# Input_0.net
KiCad netlist of a schematic drawn in Altium Designer
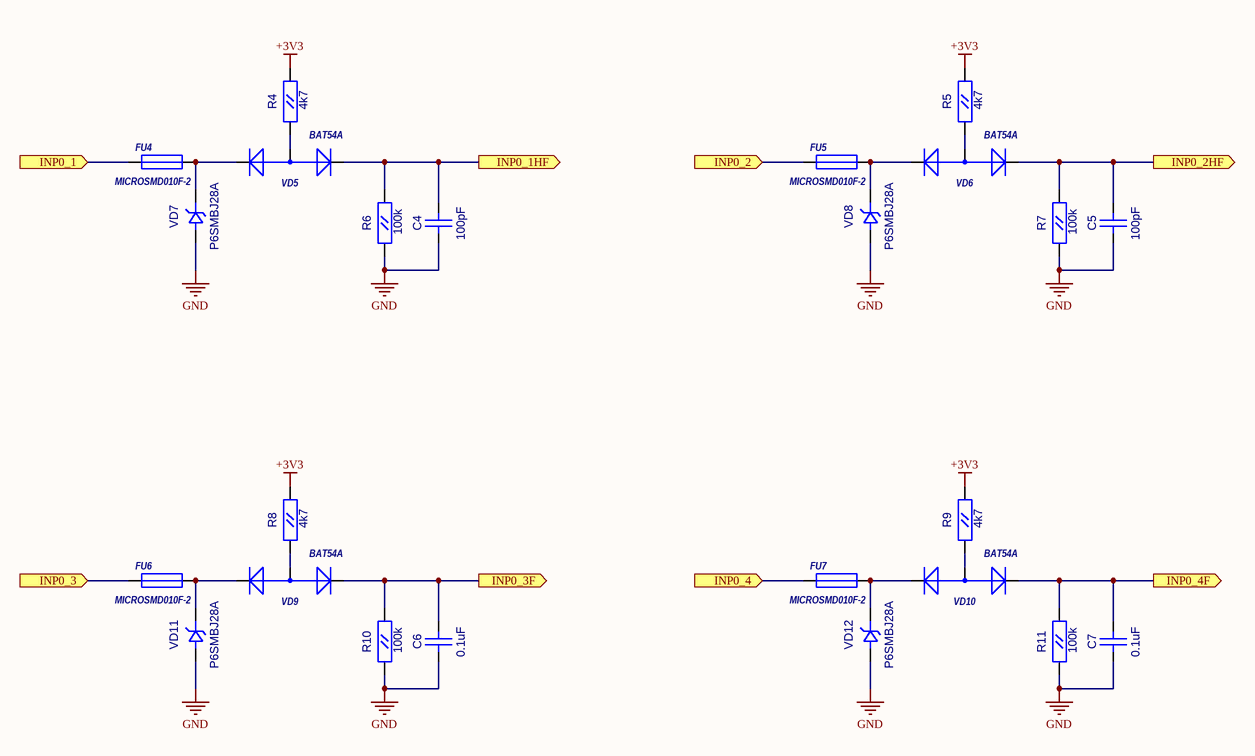
[diagram p0: Input_0.SchDoc]

(export (version "E")
  (design (tool "Eeschema 10.0.6"))
  (components
    (comp (ref "C4")
      (value "100pF")
      (footprint "CC0603")
      (description "CC0603")
      (libsource (lib "gprs_modem_2") (part "CC0603"))
    )
    (comp (ref "C5")
      (value "100pF")
      (footprint "CC0603")
      (description "CC0603")
      (libsource (lib "gprs_modem_2") (part "CC0603"))
    )
    (comp (ref "C6")
      (value "0.1uF")
      (footprint "CC0603")
      (description "CC0603")
      (libsource (lib "gprs_modem_2") (part "CC0603"))
    )
    (comp (ref "C7")
      (value "0.1uF")
      (footprint "CC0603")
      (description "CC0603")
      (libsource (lib "gprs_modem_2") (part "CC0603"))
    )
    (comp (ref "FU4")
      (value "MICROSMD010F-2")
      (footprint "RC1210")
      (description "MICROSMD")
      (libsource (lib "gprs_modem_2") (part "MICROSMD"))
    )
    (comp (ref "FU5")
      (value "MICROSMD010F-2")
      (footprint "RC1210")
      (description "MICROSMD")
      (libsource (lib "gprs_modem_2") (part "MICROSMD"))
    )
    (comp (ref "FU6")
      (value "MICROSMD010F-2")
      (footprint "RC1210")
      (description "MICROSMD")
      (libsource (lib "gprs_modem_2") (part "MICROSMD"))
    )
    (comp (ref "FU7")
      (value "MICROSMD010F-2")
      (footprint "RC1210")
      (description "MICROSMD")
      (libsource (lib "gprs_modem_2") (part "MICROSMD"))
    )
    (comp (ref "R4")
      (value "4k7")
      (footprint "RC0603")
      (description "RC0603")
      (libsource (lib "gprs_modem_2") (part "RC0603"))
    )
    (comp (ref "R5")
      (value "4k7")
      (footprint "RC0603")
      (description "RC0603")
      (libsource (lib "gprs_modem_2") (part "RC0603"))
    )
    (comp (ref "R6")
      (value "100k")
      (footprint "RC0603")
      (description "RC0603")
      (libsource (lib "gprs_modem_2") (part "RC0603"))
    )
    (comp (ref "R7")
      (value "100k")
      (footprint "RC0603")
      (description "RC0603")
      (libsource (lib "gprs_modem_2") (part "RC0603"))
    )
    (comp (ref "R8")
      (value "4k7")
      (footprint "RC0603")
      (description "RC0603")
      (libsource (lib "gprs_modem_2") (part "RC0603"))
    )
    (comp (ref "R9")
      (value "4k7")
      (footprint "RC0603")
      (description "RC0603")
      (libsource (lib "gprs_modem_2") (part "RC0603"))
    )
    (comp (ref "R10")
      (value "100k")
      (footprint "RC0603")
      (description "RC0603")
      (libsource (lib "gprs_modem_2") (part "RC0603"))
    )
    (comp (ref "R11")
      (value "100k")
      (footprint "RC0603")
      (description "RC0603")
      (libsource (lib "gprs_modem_2") (part "RC0603"))
    )
    (comp (ref "VD5")
      (value "BAT54A")
      (footprint "SOT-23(123)")
      (description "1.0 Ampere General Purpose Rectifier")
      (libsource (lib "gprs_modem_2") (part "BAT54A"))
    )
    (comp (ref "VD6")
      (value "BAT54A")
      (footprint "SOT-23(123)")
      (description "1.0 Ampere General Purpose Rectifier")
      (libsource (lib "gprs_modem_2") (part "BAT54A"))
    )
    (comp (ref "VD7")
      (value "P6SMBJ28A")
      (footprint "SMB")
      (description "SMBJ")
      (libsource (lib "gprs_modem_2") (part "SMBJ"))
    )
    (comp (ref "VD8")
      (value "P6SMBJ28A")
      (footprint "SMB")
      (description "SMBJ")
      (libsource (lib "gprs_modem_2") (part "SMBJ"))
    )
    (comp (ref "VD9")
      (value "BAT54A")
      (footprint "SOT-23(123)")
      (description "1.0 Ampere General Purpose Rectifier")
      (libsource (lib "gprs_modem_2") (part "BAT54A"))
    )
    (comp (ref "VD10")
      (value "BAT54A")
      (footprint "SOT-23(123)")
      (description "1.0 Ampere General Purpose Rectifier")
      (libsource (lib "gprs_modem_2") (part "BAT54A"))
    )
    (comp (ref "VD11")
      (value "P6SMBJ28A")
      (footprint "SMB")
      (description "SMBJ")
      (libsource (lib "gprs_modem_2") (part "SMBJ"))
    )
    (comp (ref "VD12")
      (value "P6SMBJ28A")
      (footprint "SMB")
      (description "SMBJ")
      (libsource (lib "gprs_modem_2") (part "SMBJ"))
    )
  )
  (nets
    (net (code "1") (name "+3V3") (class "Default")
      (node (ref "R4") (pin "2") (pinfunction "B_2") (pintype "passive"))
      (node (ref "R5") (pin "2") (pinfunction "B_2") (pintype "passive"))
      (node (ref "R8") (pin "2") (pinfunction "B_2") (pintype "passive"))
      (node (ref "R9") (pin "2") (pinfunction "B_2") (pintype "passive"))
    )
    (net (code "2") (name "/INP0_1") (class "Default") (node (ref "FU4") (pin "1") (pintype "passive")))
    (net (code "3") (name "/INP0_1HF") (class "Default")
      (node (ref "C4") (pin "2") (pinfunction "B_2") (pintype "passive"))
      (node (ref "R6") (pin "2") (pinfunction "B_2") (pintype "passive"))
      (node (ref "VD5") (pin "1") (pinfunction "K_1") (pintype "passive"))
    )
    (net (code "4") (name "/INP0_2") (class "Default") (node (ref "FU5") (pin "1") (pintype "passive")))
    (net (code "5") (name "/INP0_2HF") (class "Default")
      (node (ref "C5") (pin "2") (pinfunction "B_2") (pintype "passive"))
      (node (ref "R7") (pin "2") (pinfunction "B_2") (pintype "passive"))
      (node (ref "VD6") (pin "1") (pinfunction "K_1") (pintype "passive"))
    )
    (net (code "6") (name "/INP0_3") (class "Default") (node (ref "FU6") (pin "1") (pintype "passive")))
    (net (code "7") (name "/INP0_3F") (class "Default")
      (node (ref "C6") (pin "2") (pinfunction "B_2") (pintype "passive"))
      (node (ref "R10") (pin "2") (pinfunction "B_2") (pintype "passive"))
      (node (ref "VD9") (pin "1") (pinfunction "K_1") (pintype "passive"))
    )
    (net (code "8") (name "/INP0_4") (class "Default") (node (ref "FU7") (pin "1") (pintype "passive")))
    (net (code "9") (name "/INP0_4F") (class "Default")
      (node (ref "C7") (pin "2") (pinfunction "B_2") (pintype "passive"))
      (node (ref "R11") (pin "2") (pinfunction "B_2") (pintype "passive"))
      (node (ref "VD10") (pin "1") (pinfunction "K_1") (pintype "passive"))
    )
    (net (code "10") (name "GND") (class "Default")
      (node (ref "C4") (pin "1") (pinfunction "A_1") (pintype "passive"))
      (node (ref "C5") (pin "1") (pinfunction "A_1") (pintype "passive"))
      (node (ref "C6") (pin "1") (pinfunction "A_1") (pintype "passive"))
      (node (ref "C7") (pin "1") (pinfunction "A_1") (pintype "passive"))
      (node (ref "R10") (pin "1") (pinfunction "A_1") (pintype "passive"))
      (node (ref "R11") (pin "1") (pinfunction "A_1") (pintype "passive"))
      (node (ref "R6") (pin "1") (pinfunction "A_1") (pintype "passive"))
      (node (ref "R7") (pin "1") (pinfunction "A_1") (pintype "passive"))
      (node (ref "VD11") (pin "1") (pinfunction "A_1") (pintype "passive"))
      (node (ref "VD12") (pin "1") (pinfunction "A_1") (pintype "passive"))
      (node (ref "VD7") (pin "1") (pinfunction "A_1") (pintype "passive"))
      (node (ref "VD8") (pin "1") (pinfunction "A_1") (pintype "passive"))
    )
    (net (code "11") (name "Net-(R4-A)") (class "Default")
      (node (ref "R4") (pin "1") (pinfunction "A_1") (pintype "passive"))
      (node (ref "VD5") (pin "3") (pinfunction "A_3") (pintype "passive"))
    )
    (net (code "12") (name "Net-(R5-A)") (class "Default")
      (node (ref "R5") (pin "1") (pinfunction "A_1") (pintype "passive"))
      (node (ref "VD6") (pin "3") (pinfunction "A_3") (pintype "passive"))
    )
    (net (code "13") (name "Net-(R8-A)") (class "Default")
      (node (ref "R8") (pin "1") (pinfunction "A_1") (pintype "passive"))
      (node (ref "VD9") (pin "3") (pinfunction "A_3") (pintype "passive"))
    )
    (net (code "14") (name "Net-(R9-A)") (class "Default")
      (node (ref "R9") (pin "1") (pinfunction "A_1") (pintype "passive"))
      (node (ref "VD10") (pin "3") (pinfunction "A_3") (pintype "passive"))
    )
    (net (code "15") (name "Net-(VD7-K)") (class "Default")
      (node (ref "FU4") (pin "2") (pintype "passive"))
      (node (ref "VD5") (pin "2") (pinfunction "K_2") (pintype "passive"))
      (node (ref "VD7") (pin "2") (pinfunction "K_2") (pintype "passive"))
    )
    (net (code "16") (name "Net-(VD8-K)") (class "Default")
      (node (ref "FU5") (pin "2") (pintype "passive"))
      (node (ref "VD6") (pin "2") (pinfunction "K_2") (pintype "passive"))
      (node (ref "VD8") (pin "2") (pinfunction "K_2") (pintype "passive"))
    )
    (net (code "17") (name "Net-(VD11-K)") (class "Default")
      (node (ref "FU6") (pin "2") (pintype "passive"))
      (node (ref "VD11") (pin "2") (pinfunction "K_2") (pintype "passive"))
      (node (ref "VD9") (pin "2") (pinfunction "K_2") (pintype "passive"))
    )
    (net (code "18") (name "Net-(VD12-K)") (class "Default")
      (node (ref "FU7") (pin "2") (pintype "passive"))
      (node (ref "VD10") (pin "2") (pinfunction "K_2") (pintype "passive"))
      (node (ref "VD12") (pin "2") (pinfunction "K_2") (pintype "passive"))
    )
  )
)
